# SFP_Level_Translate.net
KiCad netlist of a schematic drawn in Altium Designer
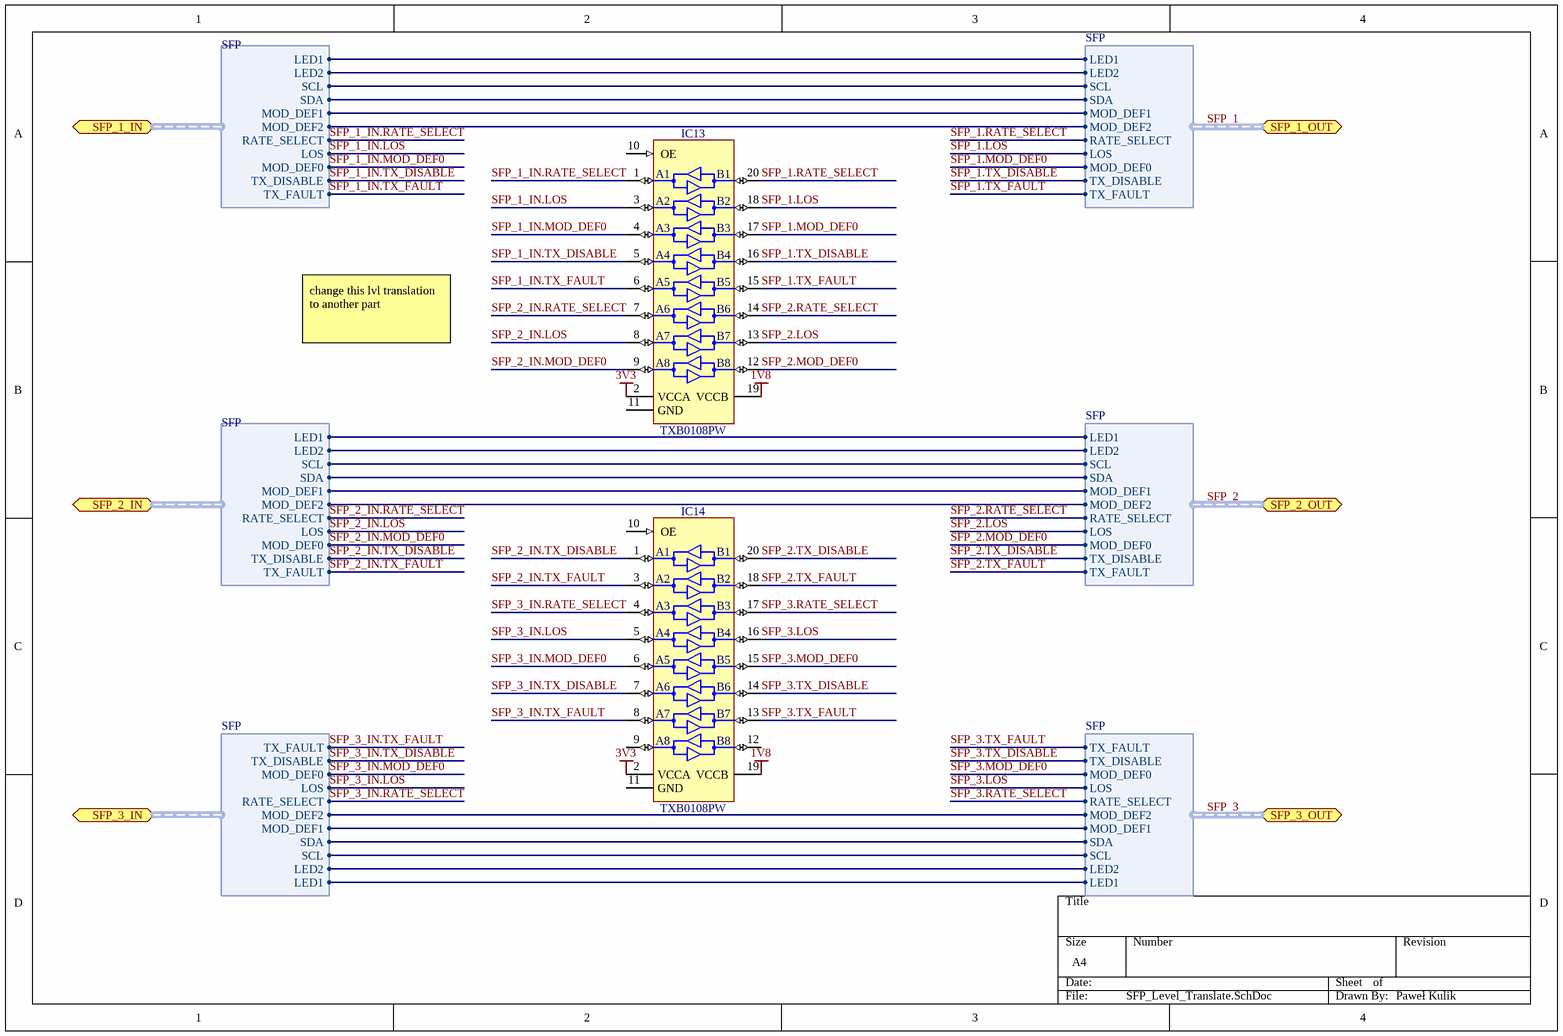
[diagram p0: SFP_Level_Translate.SchDoc]

(export (version "E")
  (design (tool "Eeschema 10.0.6"))
  (components
    (comp (ref "IC13")
      (value "TXB0108PW")
      (footprint "SOP65P640X120-20N")
      (fields (field (name "MANUFACTURER") "TEXAS INSTRUMENTS") (field (name "AUTHOR") "CERN DEM MR"))
      (libsource (lib "ICs And Semiconductors") (part "TXB0108PW"))
    )
    (comp (ref "IC14")
      (value "TXB0108PW")
      (footprint "SOP65P640X120-20N")
      (fields (field (name "MANUFACTURER") "TEXAS INSTRUMENTS") (field (name "AUTHOR") "CERN DEM MR"))
      (libsource (lib "ICs And Semiconductors") (part "TXB0108PW"))
    )
  )
  (nets
    (net (code "5") (name "/SFP_1.LOS") (class "Default")
      (node (ref "IC13") (pin "18") (pinfunction "B2_18") (pintype "bidirectional"))
    )
    (net (code "6") (name "/SFP_1.MOD_DEF0") (class "Default")
      (node (ref "IC13") (pin "17") (pinfunction "B3_17") (pintype "bidirectional"))
    )
    (net (code "7") (name "/SFP_1.RATE_SELECT") (class "Default")
      (node (ref "IC13") (pin "20") (pinfunction "B1_20") (pintype "bidirectional"))
    )
    (net (code "8") (name "/SFP_1.TX_DISABLE") (class "Default")
      (node (ref "IC13") (pin "16") (pinfunction "B4_16") (pintype "bidirectional"))
    )
    (net (code "9") (name "/SFP_1.TX_FAULT") (class "Default")
      (node (ref "IC13") (pin "15") (pinfunction "B5_15") (pintype "bidirectional"))
    )
    (net (code "10") (name "/SFP_1_IN.LOS") (class "Default")
      (node (ref "IC13") (pin "3") (pinfunction "A2_3") (pintype "bidirectional"))
    )
    (net (code "11") (name "/SFP_1_IN.MOD_DEF0") (class "Default")
      (node (ref "IC13") (pin "4") (pinfunction "A3_4") (pintype "bidirectional"))
    )
    (net (code "12") (name "/SFP_1_IN.RATE_SELECT") (class "Default")
      (node (ref "IC13") (pin "1") (pinfunction "A1_1") (pintype "bidirectional"))
    )
    (net (code "13") (name "/SFP_1_IN.TX_DISABLE") (class "Default")
      (node (ref "IC13") (pin "5") (pinfunction "A4_5") (pintype "bidirectional"))
    )
    (net (code "14") (name "/SFP_1_IN.TX_FAULT") (class "Default")
      (node (ref "IC13") (pin "6") (pinfunction "A5_6") (pintype "bidirectional"))
    )
    (net (code "16") (name "/SFP_2.LOS") (class "Default")
      (node (ref "IC13") (pin "13") (pinfunction "B7_13") (pintype "bidirectional"))
    )
    (net (code "17") (name "/SFP_2.MOD_DEF0") (class "Default")
      (node (ref "IC13") (pin "12") (pinfunction "B8_12") (pintype "bidirectional"))
    )
    (net (code "18") (name "/SFP_2.RATE_SELECT") (class "Default")
      (node (ref "IC13") (pin "14") (pinfunction "B6_14") (pintype "bidirectional"))
    )
    (net (code "19") (name "/SFP_2.TX_DISABLE") (class "Default")
      (node (ref "IC14") (pin "20") (pinfunction "B1_20") (pintype "bidirectional"))
    )
    (net (code "20") (name "/SFP_2.TX_FAULT") (class "Default")
      (node (ref "IC14") (pin "18") (pinfunction "B2_18") (pintype "bidirectional"))
    )
    (net (code "21") (name "/SFP_2_IN.LOS") (class "Default")
      (node (ref "IC13") (pin "8") (pinfunction "A7_8") (pintype "bidirectional"))
    )
    (net (code "22") (name "/SFP_2_IN.MOD_DEF0") (class "Default")
      (node (ref "IC13") (pin "9") (pinfunction "A8_9") (pintype "bidirectional"))
    )
    (net (code "23") (name "/SFP_2_IN.RATE_SELECT") (class "Default")
      (node (ref "IC13") (pin "7") (pinfunction "A6_7") (pintype "bidirectional"))
    )
    (net (code "24") (name "/SFP_2_IN.TX_DISABLE") (class "Default")
      (node (ref "IC14") (pin "1") (pinfunction "A1_1") (pintype "bidirectional"))
    )
    (net (code "25") (name "/SFP_2_IN.TX_FAULT") (class "Default")
      (node (ref "IC14") (pin "3") (pinfunction "A2_3") (pintype "bidirectional"))
    )
    (net (code "27") (name "/SFP_3.LOS") (class "Default")
      (node (ref "IC14") (pin "16") (pinfunction "B4_16") (pintype "bidirectional"))
    )
    (net (code "28") (name "/SFP_3.MOD_DEF0") (class "Default")
      (node (ref "IC14") (pin "15") (pinfunction "B5_15") (pintype "bidirectional"))
    )
    (net (code "29") (name "/SFP_3.RATE_SELECT") (class "Default")
      (node (ref "IC14") (pin "17") (pinfunction "B3_17") (pintype "bidirectional"))
    )
    (net (code "30") (name "/SFP_3.TX_DISABLE") (class "Default")
      (node (ref "IC14") (pin "14") (pinfunction "B6_14") (pintype "bidirectional"))
    )
    (net (code "31") (name "/SFP_3.TX_FAULT") (class "Default")
      (node (ref "IC14") (pin "13") (pinfunction "B7_13") (pintype "bidirectional"))
    )
    (net (code "32") (name "/SFP_3_IN.LOS") (class "Default")
      (node (ref "IC14") (pin "5") (pinfunction "A4_5") (pintype "bidirectional"))
    )
    (net (code "33") (name "/SFP_3_IN.MOD_DEF0") (class "Default")
      (node (ref "IC14") (pin "6") (pinfunction "A5_6") (pintype "bidirectional"))
    )
    (net (code "34") (name "/SFP_3_IN.RATE_SELECT") (class "Default")
      (node (ref "IC14") (pin "4") (pinfunction "A3_4") (pintype "bidirectional"))
    )
    (net (code "35") (name "/SFP_3_IN.TX_DISABLE") (class "Default")
      (node (ref "IC14") (pin "7") (pinfunction "A6_7") (pintype "bidirectional"))
    )
    (net (code "36") (name "/SFP_3_IN.TX_FAULT") (class "Default")
      (node (ref "IC14") (pin "8") (pinfunction "A7_8") (pintype "bidirectional"))
    )
    (net (code "39") (name "1V8") (class "Default")
      (node (ref "IC13") (pin "19") (pinfunction "Vccb_19") (pintype "power_in"))
      (node (ref "IC14") (pin "19") (pinfunction "Vccb_19") (pintype "power_in"))
    )
    (net (code "40") (name "3V3") (class "Default")
      (node (ref "IC13") (pin "2") (pinfunction "Vcca_2") (pintype "power_in"))
      (node (ref "IC14") (pin "2") (pinfunction "Vcca_2") (pintype "power_in"))
    )
    (net (code "41") (name "unconnected-(IC13-GND-Pad11)") (class "Default")
      (node (ref "IC13") (pin "11") (pinfunction "GND_11") (pintype "power_in"))
    )
    (net (code "42") (name "unconnected-(IC13-OE-Pad10)") (class "Default")
      (node (ref "IC13") (pin "10") (pinfunction "OE_10") (pintype "input"))
    )
    (net (code "43") (name "unconnected-(IC14-A8-Pad9)") (class "Default")
      (node (ref "IC14") (pin "9") (pinfunction "A8_9") (pintype "bidirectional"))
    )
    (net (code "44") (name "unconnected-(IC14-B8-Pad12)") (class "Default")
      (node (ref "IC14") (pin "12") (pinfunction "B8_12") (pintype "bidirectional"))
    )
    (net (code "45") (name "unconnected-(IC14-GND-Pad11)") (class "Default")
      (node (ref "IC14") (pin "11") (pinfunction "GND_11") (pintype "power_in"))
    )
    (net (code "46") (name "unconnected-(IC14-OE-Pad10)") (class "Default")
      (node (ref "IC14") (pin "10") (pinfunction "OE_10") (pintype "input"))
    )
  )
)
